# drone.net
KiCad netlist of a schematic drawn in EasyEDA
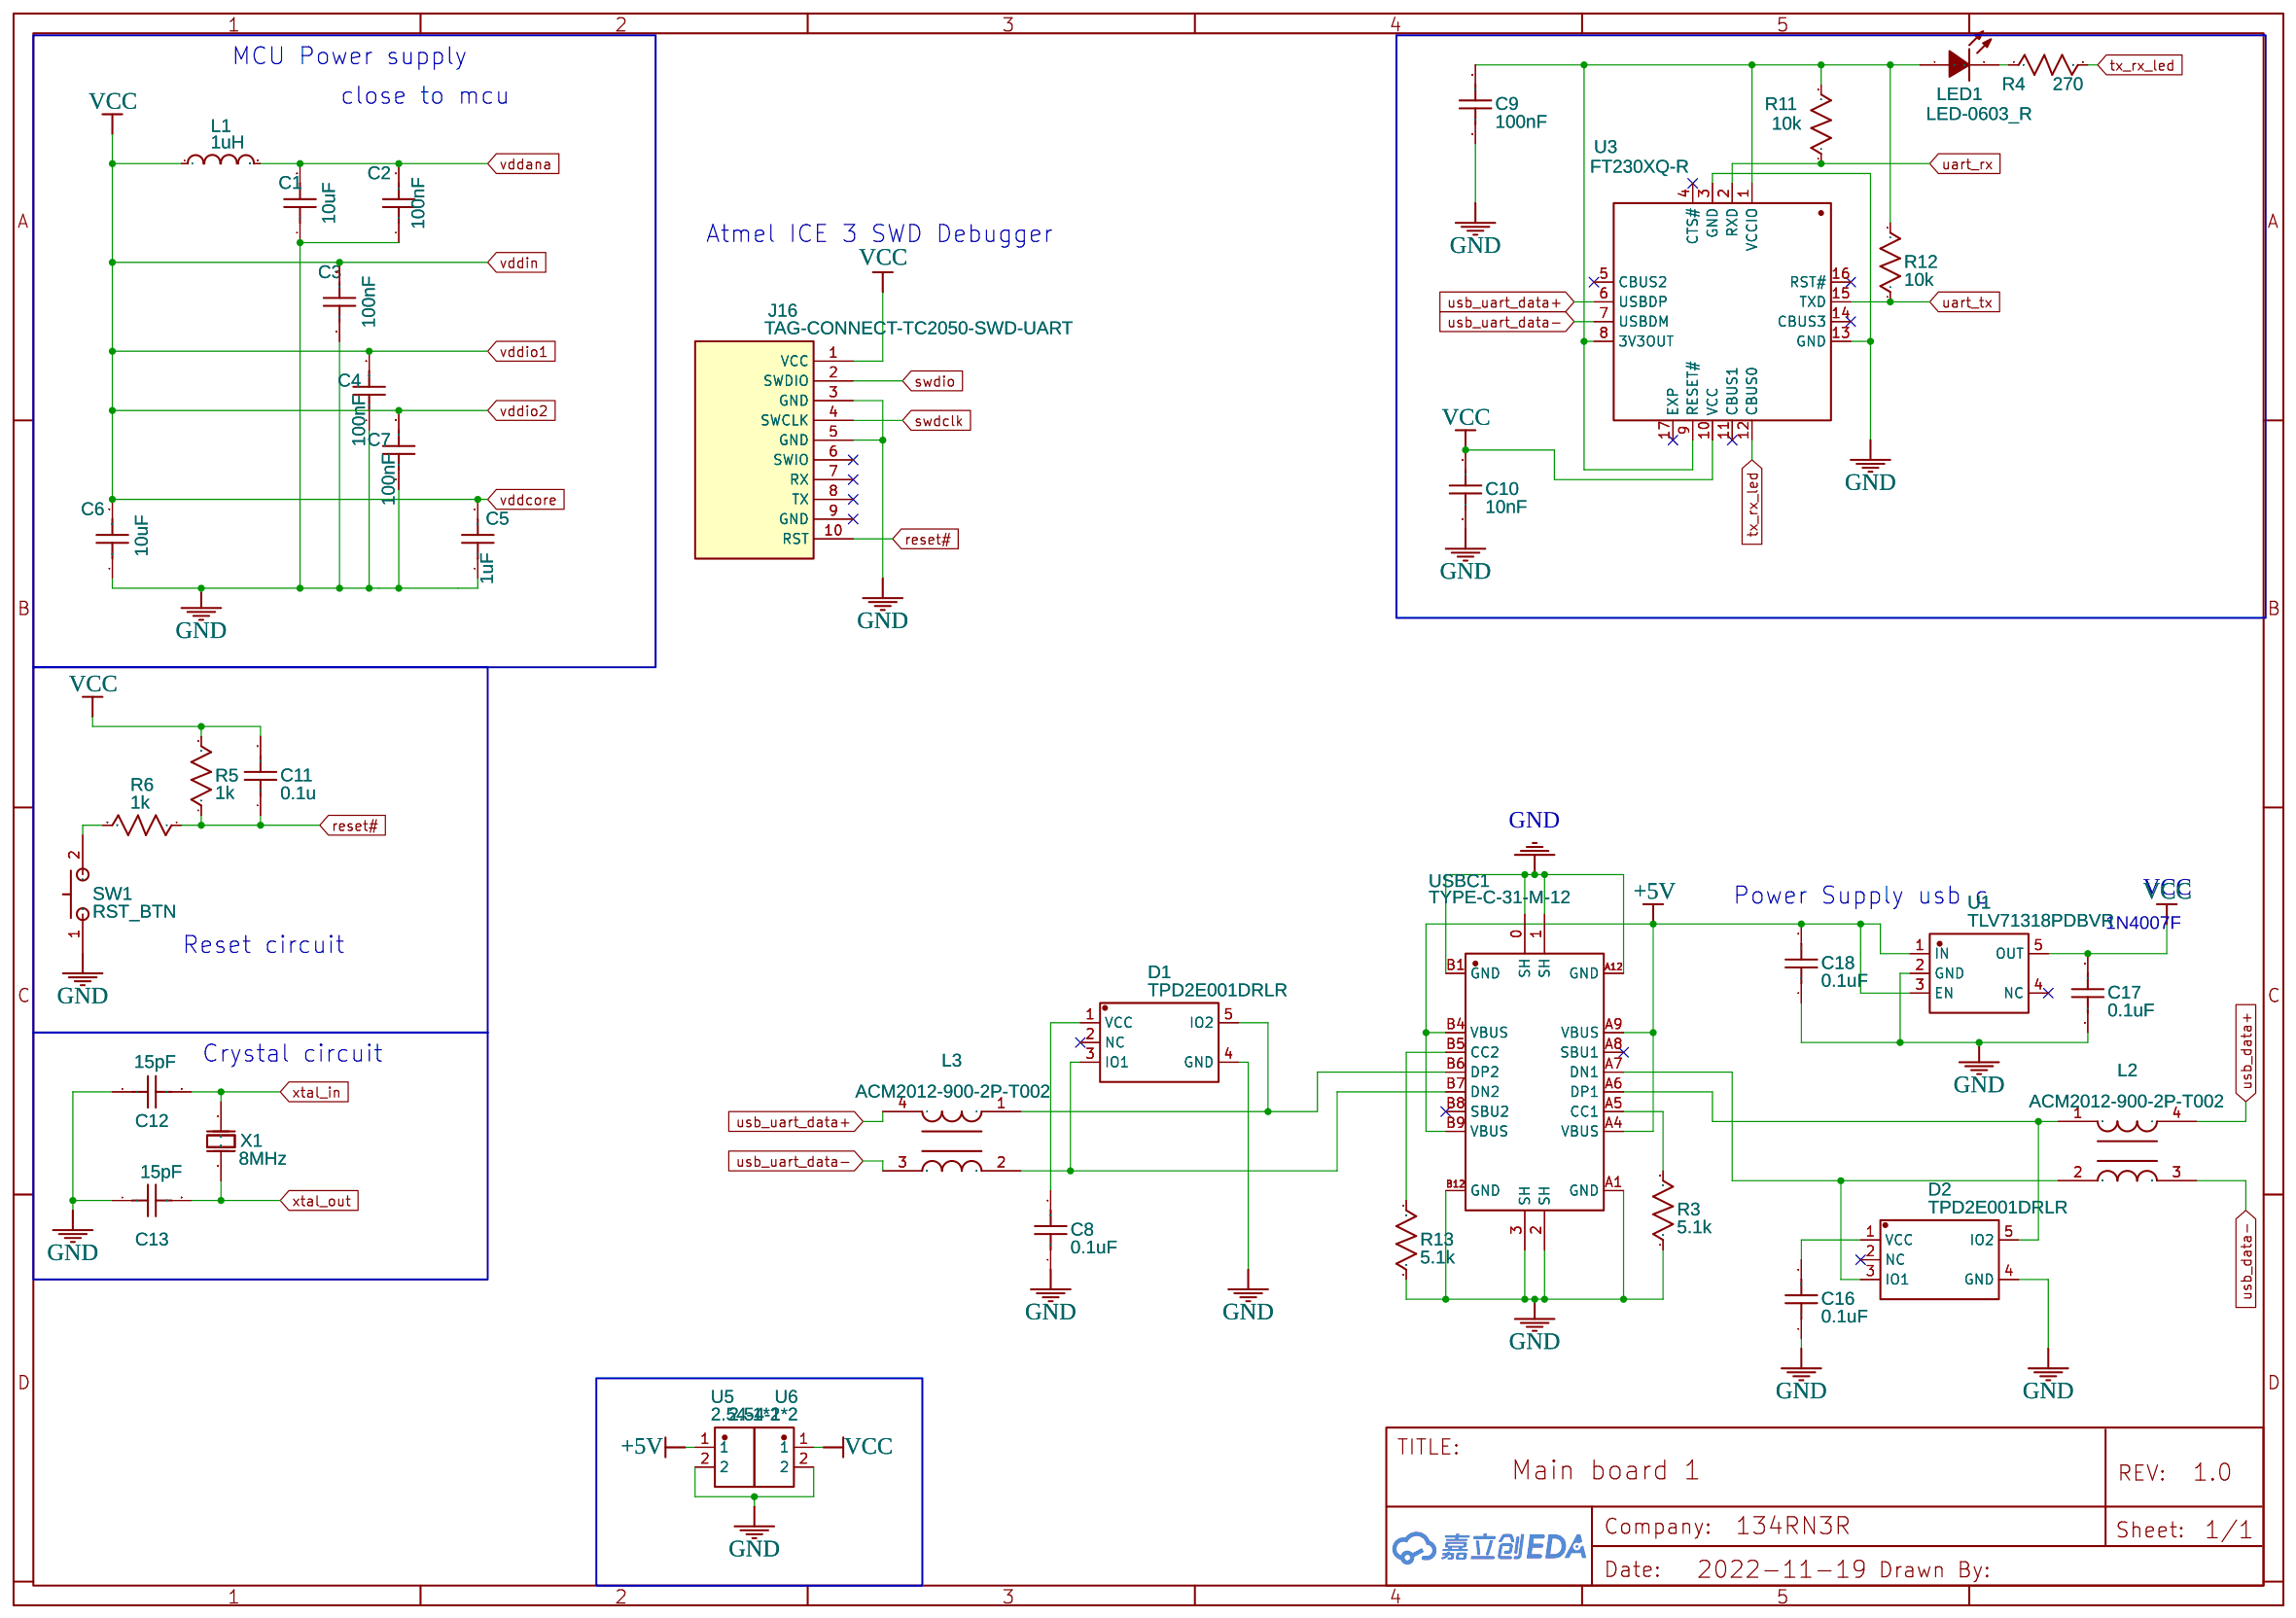
[diagram p0: main_board_1]
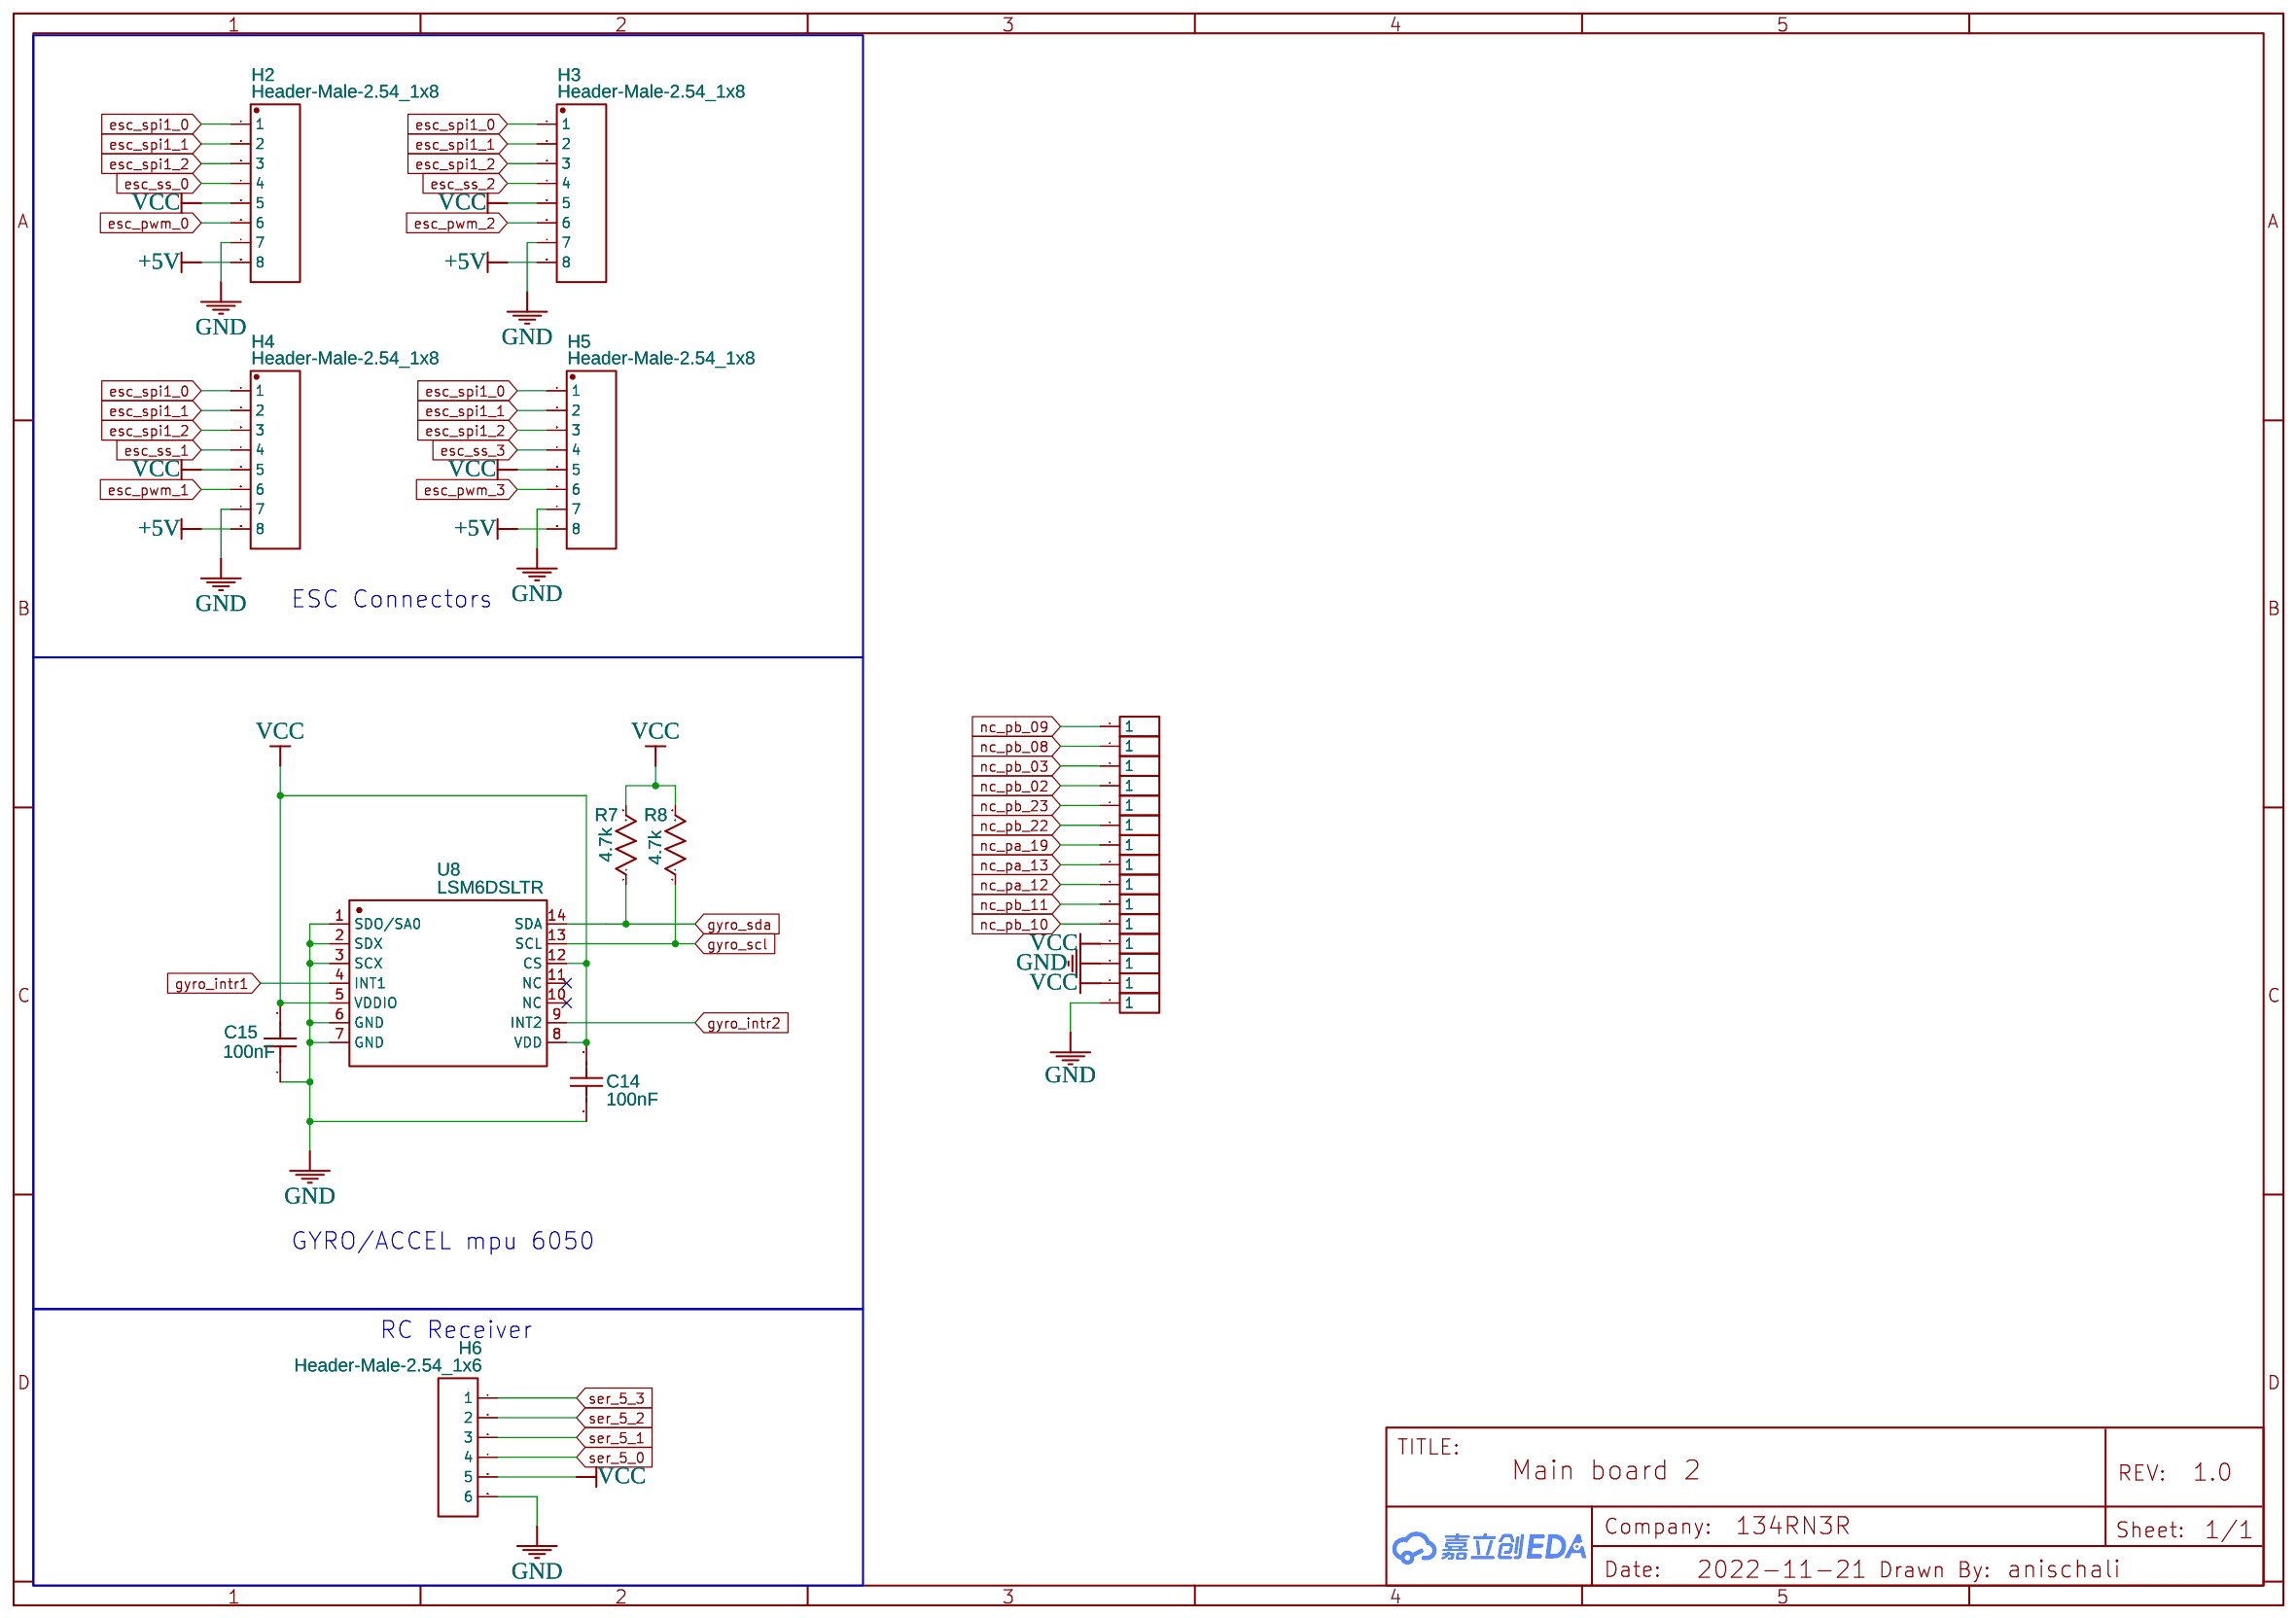
[diagram p1: main_board_2]
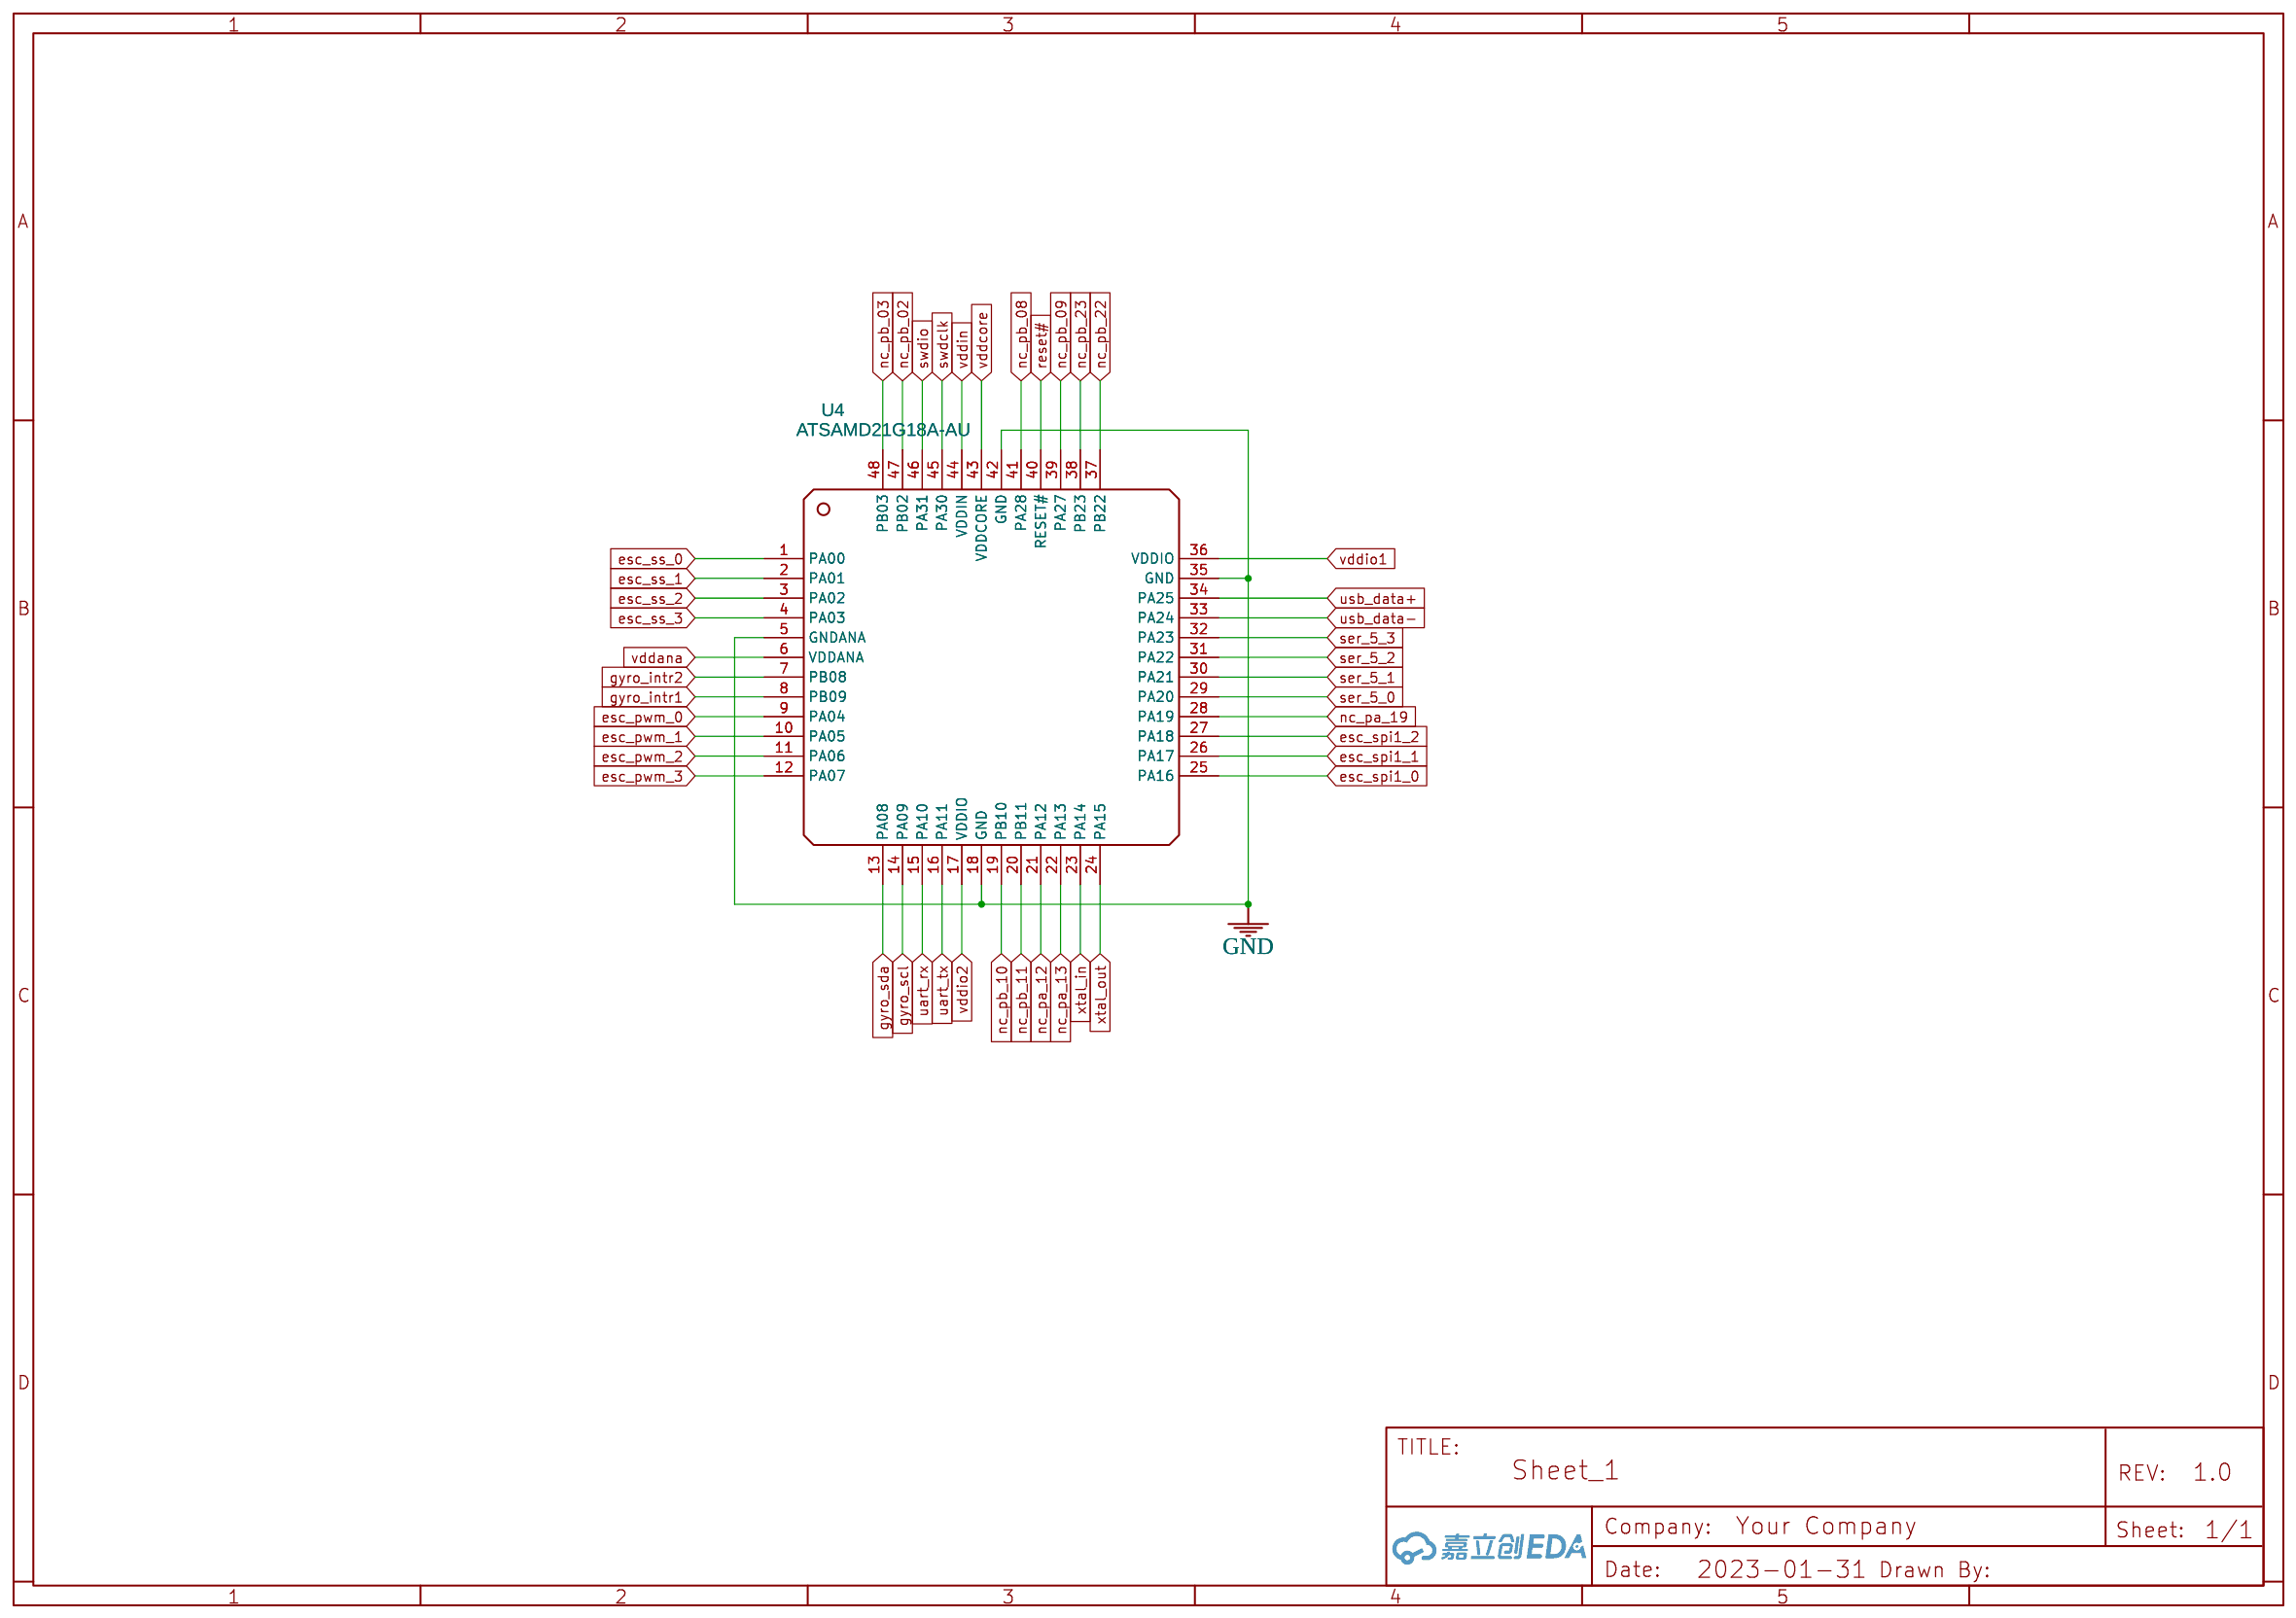
[diagram p2: cpu]

(export (version "E")
  (design (tool "Eeschema 10.0.6"))
  (components
    (comp (ref "C1") (value "10uF") (libsource (lib "") (part "C_0603_US")))
    (comp (ref "C2") (value "100nF") (libsource (lib "") (part "C_0603_US")))
    (comp (ref "C3") (value "100nF") (libsource (lib "") (part "C_0603_US")))
    (comp (ref "C4") (value "100nF") (libsource (lib "") (part "C_0603_US")))
    (comp (ref "C5") (value "1uF") (libsource (lib "") (part "C_0603_US")))
    (comp (ref "C6") (value "10uF") (libsource (lib "") (part "C_0603_US")))
    (comp (ref "C7") (value "100nF") (libsource (lib "") (part "C_0603_US")))
    (comp (ref "C8") (value "0.1uF") (libsource (lib "") (part "C_0603_US")))
    (comp (ref "C9") (value "100nF") (libsource (lib "") (part "C_0603_US")))
    (comp (ref "C10") (value "10nF") (libsource (lib "") (part "C_0603_US")))
    (comp (ref "C11") (value "0.1u") (libsource (lib "") (part "C_0603_US")))
    (comp (ref "C12") (value "15pF") (libsource (lib "") (part "C_0603_US_1")))
    (comp (ref "C13") (value "15pF") (libsource (lib "") (part "C_0603_US_1")))
    (comp (ref "C16") (value "0.1uF") (libsource (lib "") (part "C_0603_US")))
    (comp (ref "C17") (value "0.1uF") (libsource (lib "") (part "C_0603_US")))
    (comp (ref "C18") (value "0.1uF") (libsource (lib "") (part "C_0603_US")))
    (comp (ref "D1")
      (value "TPD2E001DRLR")
      (fields (field (name "BOM_Supplier Part") "C150526"))
      (libsource (lib "") (part "TPD2E001DRLR"))
    )
    (comp (ref "D2")
      (value "TPD2E001DRLR")
      (fields (field (name "BOM_Supplier Part") "C150526"))
      (libsource (lib "") (part "TPD2E001DRLR"))
    )
    (comp (ref "J16")
      (value "TAG-CONNECT-TC2050-SWD-UART")
      (libsource (lib "") (part "TAG-CONNECT-TC2050-SWD-UART"))
    )
    (comp (ref "L1") (value "1uH") (libsource (lib "") (part "L0603_US")))
    (comp (ref "L2")
      (value "ACM2012-900-2P-T002")
      (fields (field (name "BOM_Supplier Part") "C19972"))
      (libsource (lib "") (part "ACM2012-900-2P-T002_1"))
    )
    (comp (ref "L3")
      (value "ACM2012-900-2P-T002")
      (fields (field (name "BOM_Supplier Part") "C19972"))
      (libsource (lib "") (part "ACM2012-900-2P-T002"))
    )
    (comp (ref "LED1")
      (value "LED-0603_R")
      (fields
        (field (name "BOM_Manufacturer Part") "19-217/R6C-AL1M2VY/3T")
        (field (name "BOM_Supplier Part") "C72044")
      )
      (libsource (lib "") (part "LED-0603_R"))
    )
    (comp (ref "R3") (value "5.1k") (libsource (lib "") (part "R_0603_US")))
    (comp (ref "R4") (value "270") (libsource (lib "") (part "R_0603_US_2")))
    (comp (ref "R5") (value "1k") (libsource (lib "") (part "R_0603_US")))
    (comp (ref "R6") (value "1k") (libsource (lib "") (part "R_0603_US_1")))
    (comp (ref "R11") (value "10k") (libsource (lib "") (part "R_0603_US")))
    (comp (ref "R12") (value "10k") (libsource (lib "") (part "R_0603_US")))
    (comp (ref "R13") (value "5.1k") (libsource (lib "") (part "R_0603_US")))
    (comp (ref "SW1")
      (value "RST_BTN")
      (fields
        (field (name "BOM_Manufacturer Part") "SW_BUTTON_3x6_SM")
        (field (name "BOM_Supplier Part") "C9900004645")
      )
      (libsource (lib "") (part "SW_BUTTON_3X6_SM"))
    )
    (comp (ref "U1")
      (value "TLV71318PDBVR")
      (fields (field (name "BOM_Supplier Part") "C2869099"))
      (libsource (lib "") (part "TLV71318PDBVR"))
    )
    (comp (ref "U3")
      (value "FT230XQ-R")
      (fields (field (name "BOM_Supplier Part") "C128629"))
      (libsource (lib "") (part "FT230XQ-R"))
    )
    (comp (ref "U5")
      (value "2.54-1*2")
      (fields (field (name "BOM_Supplier Part") "C5116481"))
      (libsource (lib "") (part "2.54-1*2"))
    )
    (comp (ref "U6")
      (value "2.54-1*2")
      (fields (field (name "BOM_Supplier Part") "C5116481"))
      (libsource (lib "") (part "2.54-1*2_1"))
    )
    (comp (ref "USBC1")
      (value "TYPE-C-31-M-12")
      (fields (field (name "BOM_Supplier Part") "C165948"))
      (libsource (lib "") (part "TYPE-C-31-M-12"))
    )
    (comp (ref "X1")
      (value "8MHz")
      (fields
        (field (name "BOM_Manufacturer Part") "X49SD8MSB2SI")
        (field (name "BOM_Supplier Part") "C188205")
      )
      (libsource (lib "") (part "X49SD8MSB2SI"))
    )
    (comp (ref "C14") (value "100nF") (libsource (lib "") (part "C_0603_US")))
    (comp (ref "C15") (value "100nF") (libsource (lib "") (part "C_0603_US")))
    (comp (ref "H2")
      (value "Header-Male-2.54_1x8")
      (fields
        (field (name "BOM_Manufacturer Part") "210S-1*8P L=11.6MMGold-plated black")
        (field (name "BOM_Supplier Part") "C124381")
      )
      (libsource (lib "") (part "Header-Male-2.54_1x8"))
    )
    (comp (ref "H3")
      (value "Header-Male-2.54_1x8")
      (fields
        (field (name "BOM_Manufacturer Part") "210S-1*8P L=11.6MMGold-plated black")
        (field (name "BOM_Supplier Part") "C124381")
      )
      (libsource (lib "") (part "Header-Male-2.54_1x8"))
    )
    (comp (ref "H4")
      (value "Header-Male-2.54_1x8")
      (fields
        (field (name "BOM_Manufacturer Part") "210S-1*8P L=11.6MMGold-plated black")
        (field (name "BOM_Supplier Part") "C124381")
      )
      (libsource (lib "") (part "Header-Male-2.54_1x8"))
    )
    (comp (ref "H5")
      (value "Header-Male-2.54_1x8")
      (fields
        (field (name "BOM_Manufacturer Part") "210S-1*8P L=11.6MMGold-plated black")
        (field (name "BOM_Supplier Part") "C124381")
      )
      (libsource (lib "") (part "Header-Male-2.54_1x8"))
    )
    (comp (ref "H6")
      (value "Header-Male-2.54_1x6")
      (fields
        (field (name "BOM_Manufacturer Part") "2.54-1x6P直针")
        (field (name "BOM_Supplier Part") "C37208")
      )
      (libsource (lib "") (part "Header-Male-2.54_1x6"))
    )
    (comp (ref "J1")
      (value "HDR-M-2.54_1x1")
      (fields (field (name "BOM_Supplier Part") "C81276"))
      (libsource (lib "") (part "HDR-M-2.54_1x1"))
    )
    (comp (ref "J2")
      (value "HDR-M-2.54_1x1")
      (fields (field (name "BOM_Supplier Part") "C81276"))
      (libsource (lib "") (part "HDR-M-2.54_1x1"))
    )
    (comp (ref "J3")
      (value "HDR-M-2.54_1x1")
      (fields (field (name "BOM_Supplier Part") "C81276"))
      (libsource (lib "") (part "HDR-M-2.54_1x1"))
    )
    (comp (ref "J4")
      (value "HDR-M-2.54_1x1")
      (fields (field (name "BOM_Supplier Part") "C81276"))
      (libsource (lib "") (part "HDR-M-2.54_1x1"))
    )
    (comp (ref "J5")
      (value "HDR-M-2.54_1x1")
      (fields (field (name "BOM_Supplier Part") "C81276"))
      (libsource (lib "") (part "HDR-M-2.54_1x1"))
    )
    (comp (ref "J6")
      (value "HDR-M-2.54_1x1")
      (fields (field (name "BOM_Supplier Part") "C81276"))
      (libsource (lib "") (part "HDR-M-2.54_1x1"))
    )
    (comp (ref "J7")
      (value "HDR-M-2.54_1x1")
      (fields (field (name "BOM_Supplier Part") "C81276"))
      (libsource (lib "") (part "HDR-M-2.54_1x1"))
    )
    (comp (ref "J8")
      (value "HDR-M-2.54_1x1")
      (fields (field (name "BOM_Supplier Part") "C81276"))
      (libsource (lib "") (part "HDR-M-2.54_1x1"))
    )
    (comp (ref "J9")
      (value "HDR-M-2.54_1x1")
      (fields (field (name "BOM_Supplier Part") "C81276"))
      (libsource (lib "") (part "HDR-M-2.54_1x1"))
    )
    (comp (ref "J10")
      (value "HDR-M-2.54_1x1")
      (fields (field (name "BOM_Supplier Part") "C81276"))
      (libsource (lib "") (part "HDR-M-2.54_1x1"))
    )
    (comp (ref "J11")
      (value "HDR-M-2.54_1x1")
      (fields (field (name "BOM_Supplier Part") "C81276"))
      (libsource (lib "") (part "HDR-M-2.54_1x1"))
    )
    (comp (ref "J12")
      (value "HDR-M-2.54_1x1")
      (fields (field (name "BOM_Supplier Part") "C81276"))
      (libsource (lib "") (part "HDR-M-2.54_1x1"))
    )
    (comp (ref "J13")
      (value "HDR-M-2.54_1x1")
      (fields (field (name "BOM_Supplier Part") "C81276"))
      (libsource (lib "") (part "HDR-M-2.54_1x1"))
    )
    (comp (ref "J14")
      (value "HDR-M-2.54_1x1")
      (fields (field (name "BOM_Supplier Part") "C81276"))
      (libsource (lib "") (part "HDR-M-2.54_1x1"))
    )
    (comp (ref "J15")
      (value "HDR-M-2.54_1x1")
      (fields (field (name "BOM_Supplier Part") "C81276"))
      (libsource (lib "") (part "HDR-M-2.54_1x1"))
    )
    (comp (ref "R7") (value "4.7k") (libsource (lib "") (part "R_0603_US")))
    (comp (ref "R8") (value "4.7k") (libsource (lib "") (part "R_0603_US")))
    (comp (ref "U8")
      (value "LSM6DSLTR")
      (fields (field (name "BOM_Supplier Part") "C126672"))
      (libsource (lib "") (part "LSM6DSLTR"))
    )
    (comp (ref "U4")
      (value "ATSAMD21G18A-AU")
      (fields (field (name "BOM_Supplier Part") "C78624"))
      (libsource (lib "") (part "ATSAMD21G18A-AU"))
    )
  )
  (nets
    (net (code "1") (name "+5V") (class "Default")
      (node (ref "C18") (pin "2") (pinfunction "2_2") (pintype "unspecified"))
      (node (ref "H2") (pin "8") (pinfunction "8_8") (pintype "unspecified"))
      (node (ref "H3") (pin "8") (pinfunction "8_8") (pintype "unspecified"))
      (node (ref "H4") (pin "8") (pinfunction "8_8") (pintype "unspecified"))
      (node (ref "H5") (pin "8") (pinfunction "8_8") (pintype "unspecified"))
      (node (ref "U1") (pin "1") (pinfunction "IN_1") (pintype "unspecified"))
      (node (ref "U1") (pin "3") (pinfunction "EN_3") (pintype "unspecified"))
      (node (ref "U5") (pin "1") (pinfunction "1_1") (pintype "unspecified"))
      (node (ref "USBC1") (pin "A4") (pinfunction "VBUS_A4") (pintype "unspecified"))
      (node (ref "USBC1") (pin "A9") (pinfunction "VBUS_A9") (pintype "unspecified"))
      (node (ref "USBC1") (pin "B4") (pinfunction "VBUS_B4") (pintype "unspecified"))
      (node (ref "USBC1") (pin "B9") (pinfunction "VBUS_B9") (pintype "unspecified"))
    )
    (net (code "2") (name "GND") (class "Default")
      (node (ref "C1") (pin "1") (pinfunction "1_1") (pintype "unspecified"))
      (node (ref "C10") (pin "1") (pinfunction "1_1") (pintype "unspecified"))
      (node (ref "C12") (pin "1") (pinfunction "1_1") (pintype "unspecified"))
      (node (ref "C13") (pin "1") (pinfunction "1_1") (pintype "unspecified"))
      (node (ref "C14") (pin "1") (pinfunction "1_1") (pintype "unspecified"))
      (node (ref "C15") (pin "1") (pinfunction "1_1") (pintype "unspecified"))
      (node (ref "C16") (pin "1") (pinfunction "1_1") (pintype "unspecified"))
      (node (ref "C17") (pin "1") (pinfunction "1_1") (pintype "unspecified"))
      (node (ref "C18") (pin "1") (pinfunction "1_1") (pintype "unspecified"))
      (node (ref "C2") (pin "1") (pinfunction "1_1") (pintype "unspecified"))
      (node (ref "C3") (pin "1") (pinfunction "1_1") (pintype "unspecified"))
      (node (ref "C4") (pin "1") (pinfunction "1_1") (pintype "unspecified"))
      (node (ref "C5") (pin "1") (pinfunction "1_1") (pintype "unspecified"))
      (node (ref "C6") (pin "1") (pinfunction "1_1") (pintype "unspecified"))
      (node (ref "C7") (pin "1") (pinfunction "1_1") (pintype "unspecified"))
      (node (ref "C8") (pin "1") (pinfunction "1_1") (pintype "unspecified"))
      (node (ref "C9") (pin "1") (pinfunction "1_1") (pintype "unspecified"))
      (node (ref "D1") (pin "4") (pinfunction "GND_4") (pintype "unspecified"))
      (node (ref "D2") (pin "4") (pinfunction "GND_4") (pintype "unspecified"))
      (node (ref "H2") (pin "7") (pinfunction "7_7") (pintype "unspecified"))
      (node (ref "H3") (pin "7") (pinfunction "7_7") (pintype "unspecified"))
      (node (ref "H4") (pin "7") (pinfunction "7_7") (pintype "unspecified"))
      (node (ref "H5") (pin "7") (pinfunction "7_7") (pintype "unspecified"))
      (node (ref "H6") (pin "6") (pinfunction "6_6") (pintype "input"))
      (node (ref "J13") (pin "1") (pinfunction "1_1") (pintype "input"))
      (node (ref "J15") (pin "1") (pinfunction "1_1") (pintype "input"))
      (node (ref "J16") (pin "3") (pinfunction "GND_3") (pintype "output"))
      (node (ref "J16") (pin "5") (pinfunction "GND_5") (pintype "output"))
      (node (ref "R13") (pin "1") (pinfunction "1_1") (pintype "unspecified"))
      (node (ref "R3") (pin "1") (pinfunction "1_1") (pintype "unspecified"))
      (node (ref "SW1") (pin "1") (pinfunction "1_1") (pintype "unspecified"))
      (node (ref "U1") (pin "2") (pinfunction "GND_2") (pintype "unspecified"))
      (node (ref "U3") (pin "13") (pinfunction "GND_13") (pintype "unspecified"))
      (node (ref "U3") (pin "3") (pinfunction "GND_3") (pintype "unspecified"))
      (node (ref "U4") (pin "18") (pinfunction "GND_18") (pintype "unspecified"))
      (node (ref "U4") (pin "35") (pinfunction "GND_35") (pintype "unspecified"))
      (node (ref "U4") (pin "42") (pinfunction "GND_42") (pintype "unspecified"))
      (node (ref "U4") (pin "5") (pinfunction "GNDANA_5") (pintype "unspecified"))
      (node (ref "U5") (pin "2") (pinfunction "2_2") (pintype "unspecified"))
      (node (ref "U6") (pin "2") (pinfunction "2_2") (pintype "unspecified"))
      (node (ref "U8") (pin "1") (pinfunction "SDO/SA0_1") (pintype "unspecified"))
      (node (ref "U8") (pin "2") (pinfunction "SDX_2") (pintype "unspecified"))
      (node (ref "U8") (pin "3") (pinfunction "SCX_3") (pintype "unspecified"))
      (node (ref "U8") (pin "6") (pinfunction "GND_6") (pintype "unspecified"))
      (node (ref "U8") (pin "7") (pinfunction "GND_7") (pintype "unspecified"))
      (node (ref "USBC1") (pin "0") (pinfunction "SH_0") (pintype "unspecified"))
      (node (ref "USBC1") (pin "1") (pinfunction "SH_1") (pintype "unspecified"))
      (node (ref "USBC1") (pin "2") (pinfunction "SH_2") (pintype "unspecified"))
      (node (ref "USBC1") (pin "3") (pinfunction "SH_3") (pintype "unspecified"))
      (node (ref "USBC1") (pin "A1") (pinfunction "GND_A1") (pintype "unspecified"))
      (node (ref "USBC1") (pin "A12") (pinfunction "GND_A12") (pintype "unspecified"))
      (node (ref "USBC1") (pin "B1") (pinfunction "GND_B1") (pintype "unspecified"))
      (node (ref "USBC1") (pin "B12") (pinfunction "GND_B12") (pintype "unspecified"))
    )
    (net (code "3") (name "Net-(D1-IO1)") (class "Default")
      (node (ref "D1") (pin "3") (pinfunction "IO1_3") (pintype "unspecified"))
      (node (ref "L3") (pin "2") (pinfunction "2_2") (pintype "unspecified"))
      (node (ref "USBC1") (pin "B7") (pinfunction "DN2_B7") (pintype "unspecified"))
    )
    (net (code "4") (name "Net-(D1-IO2)") (class "Default")
      (node (ref "D1") (pin "5") (pinfunction "IO2_5") (pintype "unspecified"))
      (node (ref "L3") (pin "1") (pinfunction "1_1") (pintype "unspecified"))
      (node (ref "USBC1") (pin "B6") (pinfunction "DP2_B6") (pintype "unspecified"))
    )
    (net (code "5") (name "Net-(D1-VCC)") (class "Default")
      (node (ref "C8") (pin "2") (pinfunction "2_2") (pintype "unspecified"))
      (node (ref "D1") (pin "1") (pinfunction "VCC_1") (pintype "unspecified"))
    )
    (net (code "6") (name "Net-(D2-IO1)") (class "Default")
      (node (ref "D2") (pin "3") (pinfunction "IO1_3") (pintype "unspecified"))
      (node (ref "L2") (pin "2") (pinfunction "2_2") (pintype "unspecified"))
      (node (ref "USBC1") (pin "A7") (pinfunction "DN1_A7") (pintype "unspecified"))
    )
    (net (code "7") (name "Net-(D2-IO2)") (class "Default")
      (node (ref "D2") (pin "5") (pinfunction "IO2_5") (pintype "unspecified"))
      (node (ref "L2") (pin "1") (pinfunction "1_1") (pintype "unspecified"))
      (node (ref "USBC1") (pin "A6") (pinfunction "DP1_A6") (pintype "unspecified"))
    )
    (net (code "8") (name "Net-(D2-VCC)") (class "Default")
      (node (ref "C16") (pin "2") (pinfunction "2_2") (pintype "unspecified"))
      (node (ref "D2") (pin "1") (pinfunction "VCC_1") (pintype "unspecified"))
    )
    (net (code "9") (name "Net-(LED1-Pad2)") (class "Default")
      (node (ref "LED1") (pin "2") (pinfunction "2_2") (pintype "unspecified"))
      (node (ref "R4") (pin "1") (pinfunction "1_1") (pintype "unspecified"))
    )
    (net (code "10") (name "Net-(R6-Pad2)") (class "Default")
      (node (ref "R6") (pin "2") (pinfunction "2_2") (pintype "unspecified"))
      (node (ref "SW1") (pin "2") (pinfunction "2_2") (pintype "unspecified"))
    )
    (net (code "11") (name "Net-(U3-3V3OUT)") (class "Default")
      (node (ref "C9") (pin "2") (pinfunction "2_2") (pintype "unspecified"))
      (node (ref "LED1") (pin "1") (pinfunction "1_1") (pintype "unspecified"))
      (node (ref "R11") (pin "2") (pinfunction "2_2") (pintype "unspecified"))
      (node (ref "R12") (pin "2") (pinfunction "2_2") (pintype "unspecified"))
      (node (ref "U3") (pin "1") (pinfunction "VCCIO_1") (pintype "unspecified"))
      (node (ref "U3") (pin "8") (pinfunction "3V3OUT_8") (pintype "unspecified"))
      (node (ref "U3") (pin "9") (pinfunction "RESET#_9") (pintype "unspecified"))
    )
    (net (code "12") (name "Net-(USBC1-CC1)") (class "Default")
      (node (ref "R3") (pin "2") (pinfunction "2_2") (pintype "unspecified"))
      (node (ref "USBC1") (pin "A5") (pinfunction "CC1_A5") (pintype "unspecified"))
    )
    (net (code "13") (name "Net-(USBC1-CC2)") (class "Default")
      (node (ref "R13") (pin "2") (pinfunction "2_2") (pintype "unspecified"))
      (node (ref "USBC1") (pin "B5") (pinfunction "CC2_B5") (pintype "unspecified"))
    )
    (net (code "14") (name "esc_pwm_0") (class "Default")
      (node (ref "H2") (pin "6") (pinfunction "6_6") (pintype "unspecified"))
      (node (ref "U4") (pin "9") (pinfunction "PA04_9") (pintype "unspecified"))
    )
    (net (code "15") (name "esc_pwm_1") (class "Default")
      (node (ref "H4") (pin "6") (pinfunction "6_6") (pintype "unspecified"))
      (node (ref "U4") (pin "10") (pinfunction "PA05_10") (pintype "unspecified"))
    )
    (net (code "16") (name "esc_pwm_2") (class "Default")
      (node (ref "H3") (pin "6") (pinfunction "6_6") (pintype "unspecified"))
      (node (ref "U4") (pin "11") (pinfunction "PA06_11") (pintype "unspecified"))
    )
    (net (code "17") (name "esc_pwm_3") (class "Default")
      (node (ref "H5") (pin "6") (pinfunction "6_6") (pintype "unspecified"))
      (node (ref "U4") (pin "12") (pinfunction "PA07_12") (pintype "unspecified"))
    )
    (net (code "18") (name "esc_spi1_0") (class "Default")
      (node (ref "H2") (pin "1") (pinfunction "1_1") (pintype "unspecified"))
      (node (ref "H3") (pin "1") (pinfunction "1_1") (pintype "unspecified"))
      (node (ref "H4") (pin "1") (pinfunction "1_1") (pintype "unspecified"))
      (node (ref "H5") (pin "1") (pinfunction "1_1") (pintype "unspecified"))
      (node (ref "U4") (pin "25") (pinfunction "PA16_25") (pintype "unspecified"))
    )
    (net (code "19") (name "esc_spi1_1") (class "Default")
      (node (ref "H2") (pin "2") (pinfunction "2_2") (pintype "unspecified"))
      (node (ref "H3") (pin "2") (pinfunction "2_2") (pintype "unspecified"))
      (node (ref "H4") (pin "2") (pinfunction "2_2") (pintype "unspecified"))
      (node (ref "H5") (pin "2") (pinfunction "2_2") (pintype "unspecified"))
      (node (ref "U4") (pin "26") (pinfunction "PA17_26") (pintype "unspecified"))
    )
    (net (code "20") (name "esc_spi1_2") (class "Default")
      (node (ref "H2") (pin "3") (pinfunction "3_3") (pintype "unspecified"))
      (node (ref "H3") (pin "3") (pinfunction "3_3") (pintype "unspecified"))
      (node (ref "H4") (pin "3") (pinfunction "3_3") (pintype "unspecified"))
      (node (ref "H5") (pin "3") (pinfunction "3_3") (pintype "unspecified"))
      (node (ref "U4") (pin "27") (pinfunction "PA18_27") (pintype "unspecified"))
    )
    (net (code "21") (name "esc_ss_0") (class "Default")
      (node (ref "H2") (pin "4") (pinfunction "4_4") (pintype "unspecified"))
      (node (ref "U4") (pin "1") (pinfunction "PA00_1") (pintype "unspecified"))
    )
    (net (code "22") (name "esc_ss_1") (class "Default")
      (node (ref "H4") (pin "4") (pinfunction "4_4") (pintype "unspecified"))
      (node (ref "U4") (pin "2") (pinfunction "PA01_2") (pintype "unspecified"))
    )
    (net (code "23") (name "esc_ss_2") (class "Default")
      (node (ref "H3") (pin "4") (pinfunction "4_4") (pintype "unspecified"))
      (node (ref "U4") (pin "3") (pinfunction "PA02_3") (pintype "unspecified"))
    )
    (net (code "24") (name "esc_ss_3") (class "Default")
      (node (ref "H5") (pin "4") (pinfunction "4_4") (pintype "unspecified"))
      (node (ref "U4") (pin "4") (pinfunction "PA03_4") (pintype "unspecified"))
    )
    (net (code "25") (name "gyro_intr1") (class "Default")
      (node (ref "U4") (pin "8") (pinfunction "PB09_8") (pintype "unspecified"))
      (node (ref "U8") (pin "4") (pinfunction "INT1_4") (pintype "unspecified"))
    )
    (net (code "26") (name "gyro_intr2") (class "Default")
      (node (ref "U4") (pin "7") (pinfunction "PB08_7") (pintype "unspecified"))
      (node (ref "U8") (pin "9") (pinfunction "INT2_9") (pintype "unspecified"))
    )
    (net (code "27") (name "gyro_scl") (class "Default")
      (node (ref "R8") (pin "1") (pinfunction "1_1") (pintype "unspecified"))
      (node (ref "U4") (pin "14") (pinfunction "PA09_14") (pintype "unspecified"))
      (node (ref "U8") (pin "13") (pinfunction "SCL_13") (pintype "unspecified"))
    )
    (net (code "28") (name "gyro_sda") (class "Default")
      (node (ref "R7") (pin "1") (pinfunction "1_1") (pintype "unspecified"))
      (node (ref "U4") (pin "13") (pinfunction "PA08_13") (pintype "unspecified"))
      (node (ref "U8") (pin "14") (pinfunction "SDA_14") (pintype "unspecified"))
    )
    (net (code "29") (name "nc_pa_12") (class "Default")
      (node (ref "J9") (pin "1") (pinfunction "1_1") (pintype "input"))
      (node (ref "U4") (pin "21") (pinfunction "PA12_21") (pintype "unspecified"))
    )
    (net (code "30") (name "nc_pa_13") (class "Default")
      (node (ref "J8") (pin "1") (pinfunction "1_1") (pintype "input"))
      (node (ref "U4") (pin "22") (pinfunction "PA13_22") (pintype "unspecified"))
    )
    (net (code "31") (name "nc_pa_19") (class "Default")
      (node (ref "J7") (pin "1") (pinfunction "1_1") (pintype "input"))
      (node (ref "U4") (pin "28") (pinfunction "PA19_28") (pintype "unspecified"))
    )
    (net (code "32") (name "nc_pb_02") (class "Default")
      (node (ref "J4") (pin "1") (pinfunction "1_1") (pintype "input"))
      (node (ref "U4") (pin "47") (pinfunction "PB02_47") (pintype "unspecified"))
    )
    (net (code "33") (name "nc_pb_03") (class "Default")
      (node (ref "J3") (pin "1") (pinfunction "1_1") (pintype "input"))
      (node (ref "U4") (pin "48") (pinfunction "PB03_48") (pintype "unspecified"))
    )
    (net (code "34") (name "nc_pb_08") (class "Default")
      (node (ref "J2") (pin "1") (pinfunction "1_1") (pintype "input"))
      (node (ref "U4") (pin "41") (pinfunction "PA28_41") (pintype "unspecified"))
    )
    (net (code "35") (name "nc_pb_09") (class "Default")
      (node (ref "J1") (pin "1") (pinfunction "1_1") (pintype "input"))
      (node (ref "U4") (pin "39") (pinfunction "PA27_39") (pintype "unspecified"))
    )
    (net (code "36") (name "nc_pb_10") (class "Default")
      (node (ref "J11") (pin "1") (pinfunction "1_1") (pintype "input"))
      (node (ref "U4") (pin "19") (pinfunction "PB10_19") (pintype "unspecified"))
    )
    (net (code "37") (name "nc_pb_11") (class "Default")
      (node (ref "J10") (pin "1") (pinfunction "1_1") (pintype "input"))
      (node (ref "U4") (pin "20") (pinfunction "PB11_20") (pintype "unspecified"))
    )
    (net (code "38") (name "nc_pb_22") (class "Default")
      (node (ref "J6") (pin "1") (pinfunction "1_1") (pintype "input"))
      (node (ref "U4") (pin "37") (pinfunction "PB22_37") (pintype "unspecified"))
    )
    (net (code "39") (name "nc_pb_23") (class "Default")
      (node (ref "J5") (pin "1") (pinfunction "1_1") (pintype "input"))
      (node (ref "U4") (pin "38") (pinfunction "PB23_38") (pintype "unspecified"))
    )
    (net (code "40") (name "reset#") (class "Default")
      (node (ref "C11") (pin "1") (pinfunction "1_1") (pintype "unspecified"))
      (node (ref "J16") (pin "10") (pinfunction "RST_10") (pintype "unspecified"))
      (node (ref "R5") (pin "1") (pinfunction "1_1") (pintype "unspecified"))
      (node (ref "R6") (pin "1") (pinfunction "1_1") (pintype "unspecified"))
      (node (ref "U4") (pin "40") (pinfunction "RESET#_40") (pintype "unspecified"))
    )
    (net (code "41") (name "ser_5_0") (class "Default")
      (node (ref "H6") (pin "4") (pinfunction "4_4") (pintype "input"))
      (node (ref "U4") (pin "29") (pinfunction "PA20_29") (pintype "unspecified"))
    )
    (net (code "42") (name "ser_5_1") (class "Default")
      (node (ref "H6") (pin "3") (pinfunction "3_3") (pintype "input"))
      (node (ref "U4") (pin "30") (pinfunction "PA21_30") (pintype "unspecified"))
    )
    (net (code "43") (name "ser_5_2") (class "Default")
      (node (ref "H6") (pin "2") (pinfunction "2_2") (pintype "input"))
      (node (ref "U4") (pin "31") (pinfunction "PA22_31") (pintype "unspecified"))
    )
    (net (code "44") (name "ser_5_3") (class "Default")
      (node (ref "H6") (pin "1") (pinfunction "1_1") (pintype "input"))
      (node (ref "U4") (pin "32") (pinfunction "PA23_32") (pintype "unspecified"))
    )
    (net (code "45") (name "swdclk") (class "Default")
      (node (ref "J16") (pin "4") (pinfunction "SWCLK_4") (pintype "output"))
      (node (ref "U4") (pin "45") (pinfunction "PA30_45") (pintype "unspecified"))
    )
    (net (code "46") (name "swdio") (class "Default")
      (node (ref "J16") (pin "2") (pinfunction "SWDIO_2") (pintype "unspecified"))
      (node (ref "U4") (pin "46") (pinfunction "PA31_46") (pintype "unspecified"))
    )
    (net (code "47") (name "tx_rx_led") (class "Default")
      (node (ref "R4") (pin "2") (pinfunction "2_2") (pintype "unspecified"))
      (node (ref "U3") (pin "12") (pinfunction "CBUS0_12") (pintype "unspecified"))
    )
    (net (code "48") (name "uart_rx") (class "Default")
      (node (ref "R11") (pin "1") (pinfunction "1_1") (pintype "unspecified"))
      (node (ref "U3") (pin "2") (pinfunction "RXD_2") (pintype "unspecified"))
      (node (ref "U4") (pin "15") (pinfunction "PA10_15") (pintype "unspecified"))
    )
    (net (code "49") (name "uart_tx") (class "Default")
      (node (ref "R12") (pin "1") (pinfunction "1_1") (pintype "unspecified"))
      (node (ref "U3") (pin "15") (pinfunction "TXD_15") (pintype "unspecified"))
      (node (ref "U4") (pin "16") (pinfunction "PA11_16") (pintype "unspecified"))
    )
    (net (code "50") (name "unconnected-(D1-NC-Pad2)") (class "Default")
      (node (ref "D1") (pin "2") (pinfunction "NC_2") (pintype "unspecified+no_connect"))
    )
    (net (code "51") (name "unconnected-(D2-NC-Pad2)") (class "Default")
      (node (ref "D2") (pin "2") (pinfunction "NC_2") (pintype "unspecified+no_connect"))
    )
    (net (code "52") (name "unconnected-(J16-GND-Pad9)") (class "Default")
      (node (ref "J16") (pin "9") (pinfunction "GND_9") (pintype "passive+no_connect"))
    )
    (net (code "53") (name "unconnected-(J16-RX-Pad7)") (class "Default")
      (node (ref "J16") (pin "7") (pinfunction "RX_7") (pintype "output+no_connect"))
    )
    (net (code "54") (name "unconnected-(J16-SWIO-Pad6)") (class "Default")
      (node (ref "J16") (pin "6") (pinfunction "SWIO_6") (pintype "unspecified+no_connect"))
    )
    (net (code "55") (name "unconnected-(J16-TX-Pad8)") (class "Default")
      (node (ref "J16") (pin "8") (pinfunction "TX_8") (pintype "output+no_connect"))
    )
    (net (code "56") (name "unconnected-(U1-NC-Pad4)") (class "Default")
      (node (ref "U1") (pin "4") (pinfunction "NC_4") (pintype "unspecified+no_connect"))
    )
    (net (code "57") (name "unconnected-(U3-CBUS1-Pad11)") (class "Default")
      (node (ref "U3") (pin "11") (pinfunction "CBUS1_11") (pintype "unspecified+no_connect"))
    )
    (net (code "58") (name "unconnected-(U3-CBUS2-Pad5)") (class "Default")
      (node (ref "U3") (pin "5") (pinfunction "CBUS2_5") (pintype "unspecified+no_connect"))
    )
    (net (code "59") (name "unconnected-(U3-CBUS3-Pad14)") (class "Default")
      (node (ref "U3") (pin "14") (pinfunction "CBUS3_14") (pintype "unspecified+no_connect"))
    )
    (net (code "60") (name "unconnected-(U3-CTS#-Pad4)") (class "Default")
      (node (ref "U3") (pin "4") (pinfunction "CTS#_4") (pintype "unspecified+no_connect"))
    )
    (net (code "61") (name "unconnected-(U3-EXP-Pad17)") (class "Default")
      (node (ref "U3") (pin "17") (pinfunction "EXP_17") (pintype "unspecified+no_connect"))
    )
    (net (code "62") (name "unconnected-(U3-RST#-Pad16)") (class "Default")
      (node (ref "U3") (pin "16") (pinfunction "RST#_16") (pintype "unspecified+no_connect"))
    )
    (net (code "63") (name "unconnected-(U8-NC-Pad10)") (class "Default")
      (node (ref "U8") (pin "10") (pinfunction "NC_10") (pintype "unspecified+no_connect"))
    )
    (net (code "64") (name "unconnected-(U8-NC-Pad11)") (class "Default")
      (node (ref "U8") (pin "11") (pinfunction "NC_11") (pintype "unspecified+no_connect"))
    )
    (net (code "65") (name "unconnected-(USBC1-SBU1-PadA8)") (class "Default")
      (node (ref "USBC1") (pin "A8") (pinfunction "SBU1_A8") (pintype "unspecified+no_connect"))
    )
    (net (code "66") (name "unconnected-(USBC1-SBU2-PadB8)") (class "Default")
      (node (ref "USBC1") (pin "B8") (pinfunction "SBU2_B8") (pintype "unspecified+no_connect"))
    )
    (net (code "67") (name "usb_data+") (class "Default")
      (node (ref "L2") (pin "4") (pinfunction "4_4") (pintype "unspecified"))
      (node (ref "U4") (pin "34") (pinfunction "PA25_34") (pintype "unspecified"))
    )
    (net (code "68") (name "usb_data-") (class "Default")
      (node (ref "L2") (pin "3") (pinfunction "3_3") (pintype "unspecified"))
      (node (ref "U4") (pin "33") (pinfunction "PA24_33") (pintype "unspecified"))
    )
    (net (code "69") (name "usb_uart_data+") (class "Default")
      (node (ref "L3") (pin "4") (pinfunction "4_4") (pintype "unspecified"))
      (node (ref "U3") (pin "6") (pinfunction "USBDP_6") (pintype "unspecified"))
    )
    (net (code "70") (name "usb_uart_data-") (class "Default")
      (node (ref "L3") (pin "3") (pinfunction "3_3") (pintype "unspecified"))
      (node (ref "U3") (pin "7") (pinfunction "USBDM_7") (pintype "unspecified"))
    )
    (net (code "71") (name "vddana") (class "Default")
      (node (ref "C1") (pin "2") (pinfunction "2_2") (pintype "unspecified"))
      (node (ref "C2") (pin "2") (pinfunction "2_2") (pintype "unspecified"))
      (node (ref "L1") (pin "2") (pinfunction "2_2") (pintype "unspecified"))
      (node (ref "U4") (pin "6") (pinfunction "VDDANA_6") (pintype "unspecified"))
    )
    (net (code "72") (name "vddcore") (class "Default")
      (node (ref "C10") (pin "2") (pinfunction "2_2") (pintype "unspecified"))
      (node (ref "C11") (pin "2") (pinfunction "2_2") (pintype "unspecified"))
      (node (ref "C14") (pin "2") (pinfunction "2_2") (pintype "unspecified"))
      (node (ref "C15") (pin "2") (pinfunction "2_2") (pintype "unspecified"))
      (node (ref "C17") (pin "2") (pinfunction "2_2") (pintype "unspecified"))
      (node (ref "C3") (pin "2") (pinfunction "2_2") (pintype "unspecified"))
      (node (ref "C4") (pin "2") (pinfunction "2_2") (pintype "unspecified"))
      (node (ref "C5") (pin "2") (pinfunction "2_2") (pintype "unspecified"))
      (node (ref "C6") (pin "2") (pinfunction "2_2") (pintype "unspecified"))
      (node (ref "C7") (pin "2") (pinfunction "2_2") (pintype "unspecified"))
      (node (ref "H2") (pin "5") (pinfunction "5_5") (pintype "unspecified"))
      (node (ref "H3") (pin "5") (pinfunction "5_5") (pintype "unspecified"))
      (node (ref "H4") (pin "5") (pinfunction "5_5") (pintype "unspecified"))
      (node (ref "H5") (pin "5") (pinfunction "5_5") (pintype "unspecified"))
      (node (ref "H6") (pin "5") (pinfunction "5_5") (pintype "input"))
      (node (ref "J12") (pin "1") (pinfunction "1_1") (pintype "input"))
      (node (ref "J14") (pin "1") (pinfunction "1_1") (pintype "input"))
      (node (ref "J16") (pin "1") (pinfunction "VCC_1") (pintype "output"))
      (node (ref "L1") (pin "1") (pinfunction "1_1") (pintype "unspecified"))
      (node (ref "R5") (pin "2") (pinfunction "2_2") (pintype "unspecified"))
      (node (ref "R7") (pin "2") (pinfunction "2_2") (pintype "unspecified"))
      (node (ref "R8") (pin "2") (pinfunction "2_2") (pintype "unspecified"))
      (node (ref "U1") (pin "5") (pinfunction "OUT_5") (pintype "unspecified"))
      (node (ref "U3") (pin "10") (pinfunction "VCC_10") (pintype "unspecified"))
      (node (ref "U4") (pin "17") (pinfunction "VDDIO_17") (pintype "unspecified"))
      (node (ref "U4") (pin "36") (pinfunction "VDDIO_36") (pintype "unspecified"))
      (node (ref "U4") (pin "43") (pinfunction "VDDCORE_43") (pintype "unspecified"))
      (node (ref "U4") (pin "44") (pinfunction "VDDIN_44") (pintype "unspecified"))
      (node (ref "U6") (pin "1") (pinfunction "1_1") (pintype "unspecified"))
      (node (ref "U8") (pin "12") (pinfunction "CS_12") (pintype "unspecified"))
      (node (ref "U8") (pin "5") (pinfunction "VDDIO_5") (pintype "unspecified"))
      (node (ref "U8") (pin "8") (pinfunction "VDD_8") (pintype "unspecified"))
    )
    (net (code "73") (name "xtal_in") (class "Default")
      (node (ref "C12") (pin "2") (pinfunction "2_2") (pintype "unspecified"))
      (node (ref "U4") (pin "23") (pinfunction "PA14_23") (pintype "unspecified"))
      (node (ref "X1") (pin "2") (pinfunction "OSC2_2") (pintype "input"))
    )
    (net (code "74") (name "xtal_out") (class "Default")
      (node (ref "C13") (pin "2") (pinfunction "2_2") (pintype "unspecified"))
      (node (ref "U4") (pin "24") (pinfunction "PA15_24") (pintype "unspecified"))
      (node (ref "X1") (pin "1") (pinfunction "OSC1_1") (pintype "input"))
    )
  )
)
